# jtag-adapter-1-3.net
KiCad netlist of a schematic drawn in EAGLE
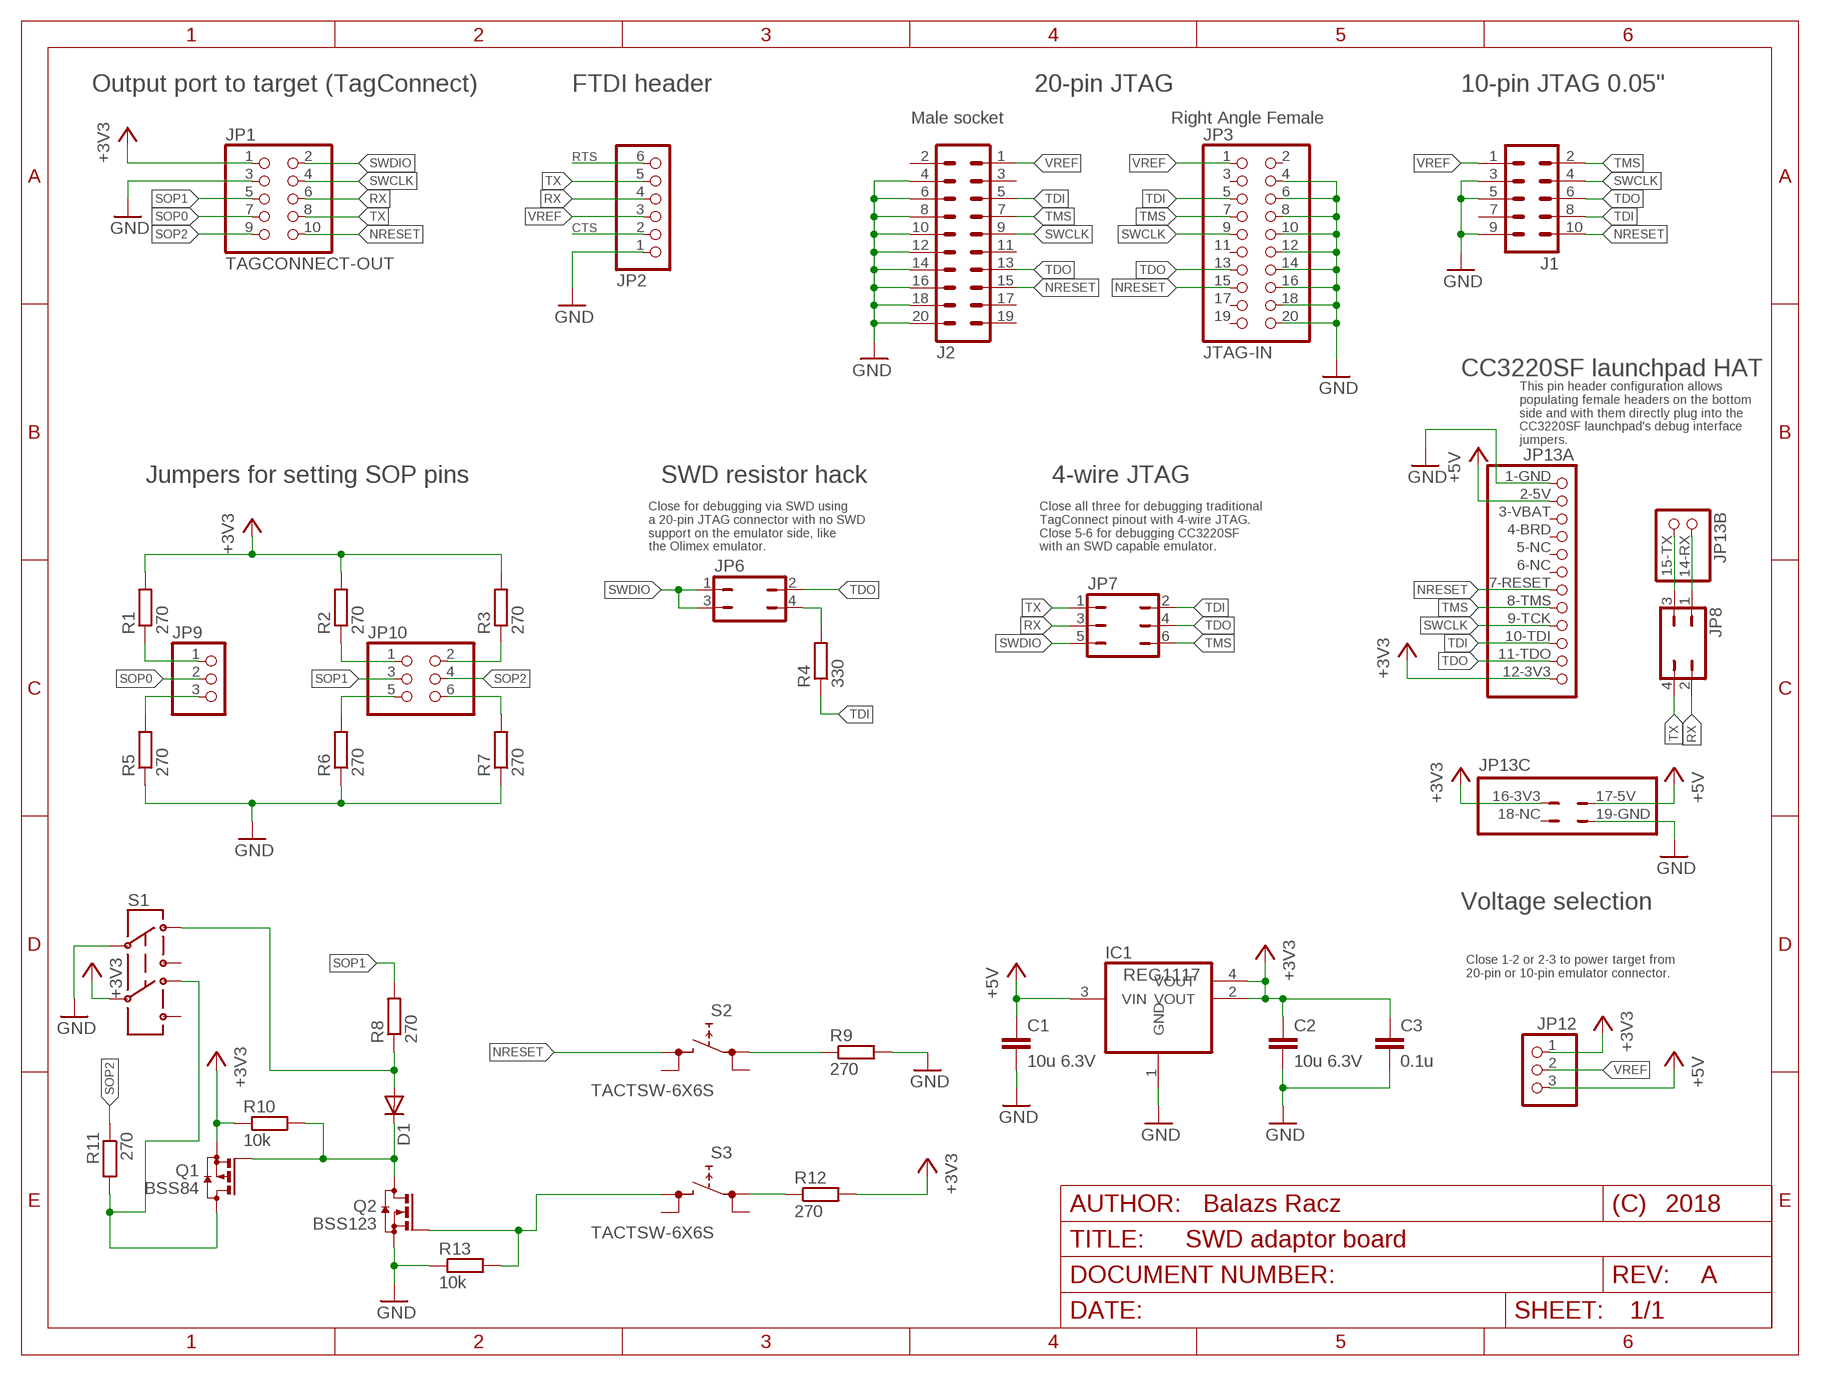
[diagram p0: schematic, sheet 1]

(export (version "E")
  (design (tool "Eeschema 10.0.6"))
  (components
    (comp (ref "C1")
      (value "10u 6.3V")
      (footprint "eagle-import:C0603K")
      (libsource (lib "eagle-import") (part "C-EUC0603K"))
    )
    (comp (ref "C2")
      (value "10u 6.3V")
      (footprint "eagle-import:C0603K")
      (libsource (lib "eagle-import") (part "C-EUC0603K"))
    )
    (comp (ref "C3")
      (value "0.1u")
      (footprint "eagle-import:C0603K")
      (libsource (lib "eagle-import") (part "C-EUC0603K"))
    )
    (comp (ref "D1")
      (value "DIODE-MINIMELF")
      (footprint "eagle-import:MINIMELF")
      (libsource (lib "eagle-import") (part "DIODE-MINIMELF"))
    )
    (comp (ref "IC1")
      (value "REG1117")
      (footprint "eagle-import:SOT223")
      (libsource (lib "eagle-import") (part "REG1117"))
    )
    (comp (ref "J1")
      (value "MA05-2_0.05X0.05")
      (footprint "eagle-import:MA05-2_0.05_X_0.05")
      (libsource (lib "eagle-import") (part "MA05-2_0.05X0.05"))
    )
    (comp (ref "J2")
      (value "MA10-2S")
      (footprint "eagle-import:MA10-2-SHROUDED")
      (libsource (lib "eagle-import") (part "MA10-2S"))
    )
    (comp (ref "JP1")
      (value "TAGCONNECT-OUT")
      (footprint "eagle-import:CON10M")
      (libsource (lib "eagle-import") (part "PINHD-2X5CN"))
    )
    (comp (ref "JP2")
      (value "PINHD-1X6")
      (footprint "eagle-import:1X06")
      (libsource (lib "eagle-import") (part "PINHD-1X6"))
    )
    (comp (ref "JP3")
      (value "JTAG-IN")
      (footprint "eagle-import:2X10_90")
      (libsource (lib "eagle-import") (part "PINHD-2X10/90"))
    )
    (comp (ref "JP6")
      (value "JP2Q")
      (footprint "eagle-import:JP2Q")
      (libsource (lib "eagle-import") (part "JP2Q"))
    )
    (comp (ref "JP7")
      (value "JP3Q")
      (footprint "eagle-import:JP3Q")
      (libsource (lib "eagle-import") (part "JP3Q"))
    )
    (comp (ref "JP8")
      (value "JP2Q")
      (footprint "eagle-import:JP2Q")
      (libsource (lib "eagle-import") (part "JP2Q"))
    )
    (comp (ref "JP9")
      (value "PINHD-1X3")
      (footprint "eagle-import:1X03")
      (libsource (lib "eagle-import") (part "PINHD-1X3"))
    )
    (comp (ref "JP10")
      (value "PINHD-2X3")
      (footprint "eagle-import:2X03")
      (libsource (lib "eagle-import") (part "PINHD-2X3"))
    )
    (comp (ref "JP12")
      (value "PINHD-1X3")
      (footprint "eagle-import:1X03")
      (libsource (lib "eagle-import") (part "PINHD-1X3"))
    )
    (comp (ref "JP13")
      (value "CC3220SF-JTAG-HAT")
      (footprint "eagle-import:JTAG-LAUNCHPAD-3220SF")
      (libsource (lib "eagle-import") (part "CC3220SF-JTAG-HAT"))
    )
    (comp (ref "Q1")
      (value "BSS84")
      (footprint "eagle-import:SOT23")
      (libsource (lib "eagle-import") (part "BSS84"))
    )
    (comp (ref "Q2")
      (value "BSS123")
      (footprint "eagle-import:SOT23")
      (libsource (lib "eagle-import") (part "BSS123"))
    )
    (comp (ref "R1")
      (value "270")
      (footprint "eagle-import:R0805")
      (libsource (lib "eagle-import") (part "R-EU_R0805"))
    )
    (comp (ref "R2")
      (value "270")
      (footprint "eagle-import:R0805")
      (libsource (lib "eagle-import") (part "R-EU_R0805"))
    )
    (comp (ref "R3")
      (value "270")
      (footprint "eagle-import:R0805")
      (libsource (lib "eagle-import") (part "R-EU_R0805"))
    )
    (comp (ref "R4")
      (value "330")
      (footprint "eagle-import:R0805")
      (libsource (lib "eagle-import") (part "R-EU_R0805"))
    )
    (comp (ref "R5")
      (value "270")
      (footprint "eagle-import:R0805")
      (libsource (lib "eagle-import") (part "R-EU_R0805"))
    )
    (comp (ref "R6")
      (value "270")
      (footprint "eagle-import:R0805")
      (libsource (lib "eagle-import") (part "R-EU_R0805"))
    )
    (comp (ref "R7")
      (value "270")
      (footprint "eagle-import:R0805")
      (libsource (lib "eagle-import") (part "R-EU_R0805"))
    )
    (comp (ref "R8")
      (value "270")
      (footprint "eagle-import:R0805")
      (libsource (lib "eagle-import") (part "R-EU_R0805"))
    )
    (comp (ref "R9")
      (value "270")
      (footprint "eagle-import:R0805")
      (libsource (lib "eagle-import") (part "R-EU_R0805"))
    )
    (comp (ref "R10")
      (value "10k")
      (footprint "eagle-import:R0805")
      (libsource (lib "eagle-import") (part "R-EU_R0805"))
    )
    (comp (ref "R11")
      (value "270")
      (footprint "eagle-import:R0805")
      (libsource (lib "eagle-import") (part "R-EU_R0805"))
    )
    (comp (ref "R12")
      (value "270")
      (footprint "eagle-import:R0805")
      (libsource (lib "eagle-import") (part "R-EU_R0805"))
    )
    (comp (ref "R13")
      (value "10k")
      (footprint "eagle-import:R0805")
      (libsource (lib "eagle-import") (part "R-EU_R0805"))
    )
    (comp (ref "S1")
      (value "SWITCH-DPDTJS202011CQN")
      (footprint "eagle-import:DPDT-2.5X3.2MM")
      (libsource (lib "eagle-import") (part "SWITCH-DPDTJS202011CQN"))
    )
    (comp (ref "S2")
      (value "TACTSW-6X6S")
      (footprint "eagle-import:TACTSW-6X6")
      (libsource (lib "eagle-import") (part "TACTSW-6X6S"))
    )
    (comp (ref "S3")
      (value "TACTSW-6X6S")
      (footprint "eagle-import:TACTSW-6X6")
      (libsource (lib "eagle-import") (part "TACTSW-6X6S"))
    )
  )
  (nets
    (net (code "1") (name "+3V3") (class "Default")
      (node (ref "C2") (pin "1") (pinfunction "1_1") (pintype "passive"))
      (node (ref "C3") (pin "1") (pinfunction "1_1") (pintype "passive"))
      (node (ref "IC1") (pin "2") (pinfunction "VOUT_2") (pintype "output"))
      (node (ref "IC1") (pin "4") (pinfunction "VOUT_4") (pintype "output"))
      (node (ref "JP1") (pin "1") (pinfunction "1_1") (pintype "passive"))
      (node (ref "JP12") (pin "1") (pinfunction "1_1") (pintype "passive"))
      (node (ref "JP13") (pin "12-3V3") (pinfunction "12_12-3V3") (pintype "passive"))
      (node (ref "JP13") (pin "16-3V3") (pinfunction "1_16-3V3") (pintype "passive"))
      (node (ref "Q1") (pin "2") (pinfunction "S_2") (pintype "passive"))
      (node (ref "R1") (pin "2") (pinfunction "2_2") (pintype "passive"))
      (node (ref "R10") (pin "1") (pinfunction "1_1") (pintype "passive"))
      (node (ref "R12") (pin "2") (pinfunction "2_2") (pintype "passive"))
      (node (ref "R2") (pin "2") (pinfunction "2_2") (pintype "passive"))
      (node (ref "R3") (pin "2") (pinfunction "2_2") (pintype "passive"))
      (node (ref "S1") (pin "5") (pinfunction "2C_5") (pintype "bidirectional"))
    )
    (net (code "2") (name "+5V") (class "Default")
      (node (ref "C1") (pin "1") (pinfunction "1_1") (pintype "passive"))
      (node (ref "IC1") (pin "3") (pinfunction "VIN_3") (pintype "input"))
      (node (ref "JP12") (pin "3") (pinfunction "3_3") (pintype "passive"))
      (node (ref "JP13") (pin "17-5V") (pinfunction "2_17-5V") (pintype "passive"))
      (node (ref "JP13") (pin "2-5V") (pinfunction "2_2-5V") (pintype "passive"))
    )
    (net (code "3") (name "/CTS") (class "Default")
      (node (ref "JP2") (pin "2") (pinfunction "2_2") (pintype "passive"))
    )
    (net (code "4") (name "/RTS") (class "Default")
      (node (ref "JP2") (pin "6") (pinfunction "6_6") (pintype "passive"))
    )
    (net (code "5") (name "GND") (class "Default")
      (node (ref "C1") (pin "2") (pinfunction "2_2") (pintype "passive"))
      (node (ref "C2") (pin "2") (pinfunction "2_2") (pintype "passive"))
      (node (ref "C3") (pin "2") (pinfunction "2_2") (pintype "passive"))
      (node (ref "IC1") (pin "1") (pinfunction "GND_1") (pintype "power_in"))
      (node (ref "J1") (pin "3") (pinfunction "3_3") (pintype "passive"))
      (node (ref "J1") (pin "5") (pinfunction "5_5") (pintype "passive"))
      (node (ref "J1") (pin "9") (pinfunction "9_9") (pintype "passive"))
      (node (ref "J2") (pin "10") (pinfunction "10_10") (pintype "passive"))
      (node (ref "J2") (pin "12") (pinfunction "12_12") (pintype "passive"))
      (node (ref "J2") (pin "14") (pinfunction "14_14") (pintype "passive"))
      (node (ref "J2") (pin "16") (pinfunction "16_16") (pintype "passive"))
      (node (ref "J2") (pin "18") (pinfunction "18_18") (pintype "passive"))
      (node (ref "J2") (pin "20") (pinfunction "20_20") (pintype "passive"))
      (node (ref "J2") (pin "4") (pinfunction "4_4") (pintype "passive"))
      (node (ref "J2") (pin "6") (pinfunction "6_6") (pintype "passive"))
      (node (ref "J2") (pin "8") (pinfunction "8_8") (pintype "passive"))
      (node (ref "JP1") (pin "3") (pinfunction "3_3") (pintype "passive"))
      (node (ref "JP13") (pin "1-GND") (pinfunction "1_1-GND") (pintype "passive"))
      (node (ref "JP13") (pin "19-GND") (pinfunction "4_19-GND") (pintype "passive"))
      (node (ref "JP2") (pin "1") (pinfunction "1_1") (pintype "passive"))
      (node (ref "JP3") (pin "10") (pinfunction "10_10") (pintype "passive"))
      (node (ref "JP3") (pin "12") (pinfunction "12_12") (pintype "passive"))
      (node (ref "JP3") (pin "14") (pinfunction "14_14") (pintype "passive"))
      (node (ref "JP3") (pin "16") (pinfunction "16_16") (pintype "passive"))
      (node (ref "JP3") (pin "18") (pinfunction "18_18") (pintype "passive"))
      (node (ref "JP3") (pin "20") (pinfunction "20_20") (pintype "passive"))
      (node (ref "JP3") (pin "4") (pinfunction "4_4") (pintype "passive"))
      (node (ref "JP3") (pin "6") (pinfunction "6_6") (pintype "passive"))
      (node (ref "JP3") (pin "8") (pinfunction "8_8") (pintype "passive"))
      (node (ref "Q2") (pin "2") (pinfunction "S_2") (pintype "passive"))
      (node (ref "R13") (pin "1") (pinfunction "1_1") (pintype "passive"))
      (node (ref "R5") (pin "1") (pinfunction "1_1") (pintype "passive"))
      (node (ref "R6") (pin "1") (pinfunction "1_1") (pintype "passive"))
      (node (ref "R7") (pin "1") (pinfunction "1_1") (pintype "passive"))
      (node (ref "R9") (pin "2") (pinfunction "2_2") (pintype "passive"))
      (node (ref "S1") (pin "2") (pinfunction "1C_2") (pintype "bidirectional"))
    )
    (net (code "6") (name "NRESET") (class "Default")
      (node (ref "J1") (pin "10") (pinfunction "10_10") (pintype "passive"))
      (node (ref "J2") (pin "15") (pinfunction "15_15") (pintype "passive"))
      (node (ref "JP1") (pin "10") (pinfunction "10_10") (pintype "passive"))
      (node (ref "JP13") (pin "7-RESET") (pinfunction "7_7-RESET") (pintype "passive"))
      (node (ref "JP3") (pin "15") (pinfunction "15_15") (pintype "passive"))
      (node (ref "S2") (pin "3") (pinfunction "2.1_3") (pintype "passive"))
    )
    (net (code "7") (name "Net-(JP6-Pad4)") (class "Default")
      (node (ref "JP6") (pin "4") (pinfunction "4_4") (pintype "passive"))
      (node (ref "R4") (pin "2") (pinfunction "2_2") (pintype "passive"))
    )
    (net (code "8") (name "Net-(JP9-Pad1)") (class "Default")
      (node (ref "JP9") (pin "1") (pinfunction "1_1") (pintype "passive"))
      (node (ref "R1") (pin "1") (pinfunction "1_1") (pintype "passive"))
    )
    (net (code "9") (name "Net-(JP9-Pad3)") (class "Default")
      (node (ref "JP9") (pin "3") (pinfunction "3_3") (pintype "passive"))
      (node (ref "R5") (pin "2") (pinfunction "2_2") (pintype "passive"))
    )
    (net (code "10") (name "Net-(JP10-Pad1)") (class "Default")
      (node (ref "JP10") (pin "1") (pinfunction "1_1") (pintype "passive"))
      (node (ref "R2") (pin "1") (pinfunction "1_1") (pintype "passive"))
    )
    (net (code "11") (name "Net-(JP10-Pad2)") (class "Default")
      (node (ref "JP10") (pin "2") (pinfunction "2_2") (pintype "passive"))
      (node (ref "R3") (pin "1") (pinfunction "1_1") (pintype "passive"))
    )
    (net (code "12") (name "Net-(JP10-Pad5)") (class "Default")
      (node (ref "JP10") (pin "5") (pinfunction "5_5") (pintype "passive"))
      (node (ref "R6") (pin "2") (pinfunction "2_2") (pintype "passive"))
    )
    (net (code "13") (name "Net-(JP10-Pad6)") (class "Default")
      (node (ref "JP10") (pin "6") (pinfunction "6_6") (pintype "passive"))
      (node (ref "R7") (pin "2") (pinfunction "2_2") (pintype "passive"))
    )
    (net (code "14") (name "Net-(JP13B-1)") (class "Default")
      (node (ref "JP13") (pin "14-RX") (pinfunction "1_14-RX") (pintype "passive"))
      (node (ref "JP8") (pin "1") (pinfunction "1_1") (pintype "passive"))
    )
    (net (code "15") (name "Net-(JP13B-2)") (class "Default")
      (node (ref "JP13") (pin "15-TX") (pinfunction "2_15-TX") (pintype "passive"))
      (node (ref "JP8") (pin "3") (pinfunction "3_3") (pintype "passive"))
    )
    (net (code "16") (name "Net-(Q1-D)") (class "Default")
      (node (ref "Q1") (pin "3") (pinfunction "D_3") (pintype "passive"))
      (node (ref "R11") (pin "2") (pinfunction "2_2") (pintype "passive"))
      (node (ref "S1") (pin "4") (pinfunction "2A_4") (pintype "bidirectional"))
    )
    (net (code "17") (name "Net-(Q1-G)") (class "Default")
      (node (ref "D1") (pin "C") (pinfunction "C_C") (pintype "passive"))
      (node (ref "Q1") (pin "1") (pinfunction "G_1") (pintype "passive"))
      (node (ref "Q2") (pin "3") (pinfunction "D_3") (pintype "passive"))
      (node (ref "R10") (pin "2") (pinfunction "2_2") (pintype "passive"))
    )
    (net (code "18") (name "Net-(Q2-G)") (class "Default")
      (node (ref "Q2") (pin "1") (pinfunction "G_1") (pintype "passive"))
      (node (ref "R13") (pin "2") (pinfunction "2_2") (pintype "passive"))
      (node (ref "S3") (pin "3") (pinfunction "2.1_3") (pintype "passive"))
    )
    (net (code "19") (name "Net-(S1-1A)") (class "Default")
      (node (ref "D1") (pin "A") (pinfunction "A_A") (pintype "passive"))
      (node (ref "R8") (pin "1") (pinfunction "1_1") (pintype "passive"))
      (node (ref "S1") (pin "1") (pinfunction "1A_1") (pintype "bidirectional"))
    )
    (net (code "20") (name "Net-(S2-1.1)") (class "Default")
      (node (ref "R9") (pin "1") (pinfunction "1_1") (pintype "passive"))
      (node (ref "S2") (pin "1") (pinfunction "1.1_1") (pintype "passive"))
    )
    (net (code "21") (name "Net-(S3-1.1)") (class "Default")
      (node (ref "R12") (pin "1") (pinfunction "1_1") (pintype "passive"))
      (node (ref "S3") (pin "1") (pinfunction "1.1_1") (pintype "passive"))
    )
    (net (code "22") (name "RX") (class "Default")
      (node (ref "JP1") (pin "6") (pinfunction "6_6") (pintype "passive"))
      (node (ref "JP2") (pin "4") (pinfunction "4_4") (pintype "passive"))
      (node (ref "JP7") (pin "3") (pinfunction "3_3") (pintype "passive"))
      (node (ref "JP8") (pin "2") (pinfunction "2_2") (pintype "passive"))
    )
    (net (code "23") (name "SOP0") (class "Default")
      (node (ref "JP1") (pin "7") (pinfunction "7_7") (pintype "passive"))
      (node (ref "JP9") (pin "2") (pinfunction "2_2") (pintype "passive"))
    )
    (net (code "24") (name "SOP1") (class "Default")
      (node (ref "JP1") (pin "5") (pinfunction "5_5") (pintype "passive"))
      (node (ref "JP10") (pin "3") (pinfunction "3_3") (pintype "passive"))
      (node (ref "R8") (pin "2") (pinfunction "2_2") (pintype "passive"))
    )
    (net (code "25") (name "SOP2") (class "Default")
      (node (ref "JP1") (pin "9") (pinfunction "9_9") (pintype "passive"))
      (node (ref "JP10") (pin "4") (pinfunction "4_4") (pintype "passive"))
      (node (ref "R11") (pin "1") (pinfunction "1_1") (pintype "passive"))
    )
    (net (code "26") (name "SWCLK") (class "Default")
      (node (ref "J1") (pin "4") (pinfunction "4_4") (pintype "passive"))
      (node (ref "J2") (pin "9") (pinfunction "9_9") (pintype "passive"))
      (node (ref "JP1") (pin "4") (pinfunction "4_4") (pintype "passive"))
      (node (ref "JP13") (pin "9-TCK") (pinfunction "9_9-TCK") (pintype "passive"))
      (node (ref "JP3") (pin "9") (pinfunction "9_9") (pintype "passive"))
    )
    (net (code "27") (name "SWDIO") (class "Default")
      (node (ref "JP1") (pin "2") (pinfunction "2_2") (pintype "passive"))
      (node (ref "JP6") (pin "1") (pinfunction "1_1") (pintype "passive"))
      (node (ref "JP6") (pin "3") (pinfunction "3_3") (pintype "passive"))
      (node (ref "JP7") (pin "5") (pinfunction "5_5") (pintype "passive"))
    )
    (net (code "28") (name "TDI") (class "Default")
      (node (ref "J1") (pin "8") (pinfunction "8_8") (pintype "passive"))
      (node (ref "J2") (pin "5") (pinfunction "5_5") (pintype "passive"))
      (node (ref "JP13") (pin "10-TDI") (pinfunction "10_10-TDI") (pintype "passive"))
      (node (ref "JP3") (pin "5") (pinfunction "5_5") (pintype "passive"))
      (node (ref "JP7") (pin "2") (pinfunction "2_2") (pintype "passive"))
      (node (ref "R4") (pin "1") (pinfunction "1_1") (pintype "passive"))
    )
    (net (code "29") (name "TDO") (class "Default")
      (node (ref "J1") (pin "6") (pinfunction "6_6") (pintype "passive"))
      (node (ref "J2") (pin "13") (pinfunction "13_13") (pintype "passive"))
      (node (ref "JP13") (pin "11-TDO") (pinfunction "11_11-TDO") (pintype "passive"))
      (node (ref "JP3") (pin "13") (pinfunction "13_13") (pintype "passive"))
      (node (ref "JP6") (pin "2") (pinfunction "2_2") (pintype "passive"))
      (node (ref "JP7") (pin "4") (pinfunction "4_4") (pintype "passive"))
    )
    (net (code "30") (name "TMS") (class "Default")
      (node (ref "J1") (pin "2") (pinfunction "2_2") (pintype "passive"))
      (node (ref "J2") (pin "7") (pinfunction "7_7") (pintype "passive"))
      (node (ref "JP13") (pin "8-TMS") (pinfunction "8_8-TMS") (pintype "passive"))
      (node (ref "JP3") (pin "7") (pinfunction "7_7") (pintype "passive"))
      (node (ref "JP7") (pin "6") (pinfunction "6_6") (pintype "passive"))
    )
    (net (code "31") (name "TX") (class "Default")
      (node (ref "JP1") (pin "8") (pinfunction "8_8") (pintype "passive"))
      (node (ref "JP2") (pin "5") (pinfunction "5_5") (pintype "passive"))
      (node (ref "JP7") (pin "1") (pinfunction "1_1") (pintype "passive"))
      (node (ref "JP8") (pin "4") (pinfunction "4_4") (pintype "passive"))
    )
    (net (code "32") (name "VREF") (class "Default")
      (node (ref "J1") (pin "1") (pinfunction "1_1") (pintype "passive"))
      (node (ref "J2") (pin "1") (pinfunction "1_1") (pintype "passive"))
      (node (ref "JP12") (pin "2") (pinfunction "2_2") (pintype "passive"))
      (node (ref "JP2") (pin "3") (pinfunction "3_3") (pintype "passive"))
      (node (ref "JP3") (pin "1") (pinfunction "1_1") (pintype "passive"))
    )
    (net (code "33") (name "unconnected-(J1-Pad7)") (class "Default")
      (node (ref "J1") (pin "7") (pinfunction "7_7") (pintype "passive"))
    )
    (net (code "34") (name "unconnected-(J2-Pad2)") (class "Default")
      (node (ref "J2") (pin "2") (pinfunction "2_2") (pintype "passive"))
    )
    (net (code "35") (name "unconnected-(J2-Pad3)") (class "Default")
      (node (ref "J2") (pin "3") (pinfunction "3_3") (pintype "passive"))
    )
    (net (code "36") (name "unconnected-(J2-Pad11)") (class "Default")
      (node (ref "J2") (pin "11") (pinfunction "11_11") (pintype "passive"))
    )
    (net (code "37") (name "unconnected-(J2-Pad17)") (class "Default")
      (node (ref "J2") (pin "17") (pinfunction "17_17") (pintype "passive"))
    )
    (net (code "38") (name "unconnected-(J2-Pad19)") (class "Default")
      (node (ref "J2") (pin "19") (pinfunction "19_19") (pintype "passive"))
    )
    (net (code "39") (name "unconnected-(JP3-Pad2)") (class "Default")
      (node (ref "JP3") (pin "2") (pinfunction "2_2") (pintype "passive"))
    )
    (net (code "40") (name "unconnected-(JP3-Pad3)") (class "Default")
      (node (ref "JP3") (pin "3") (pinfunction "3_3") (pintype "passive"))
    )
    (net (code "41") (name "unconnected-(JP3-Pad11)") (class "Default")
      (node (ref "JP3") (pin "11") (pinfunction "11_11") (pintype "passive"))
    )
    (net (code "42") (name "unconnected-(JP3-Pad17)") (class "Default")
      (node (ref "JP3") (pin "17") (pinfunction "17_17") (pintype "passive"))
    )
    (net (code "43") (name "unconnected-(JP3-Pad19)") (class "Default")
      (node (ref "JP3") (pin "19") (pinfunction "19_19") (pintype "passive"))
    )
    (net (code "44") (name "unconnected-(JP13A-3-Pad3-VBAT)") (class "Default")
      (node (ref "JP13") (pin "3-VBAT") (pinfunction "3_3-VBAT") (pintype "passive"))
    )
    (net (code "45") (name "unconnected-(JP13A-4-Pad4-BRD)") (class "Default")
      (node (ref "JP13") (pin "4-BRD") (pinfunction "4_4-BRD") (pintype "passive"))
    )
    (net (code "46") (name "unconnected-(JP13A-5-Pad5-NC)") (class "Default")
      (node (ref "JP13") (pin "5-NC") (pinfunction "5_5-NC") (pintype "passive"))
    )
    (net (code "47") (name "unconnected-(JP13A-6-Pad6-NC)") (class "Default")
      (node (ref "JP13") (pin "6-NC") (pinfunction "6_6-NC") (pintype "passive"))
    )
    (net (code "48") (name "unconnected-(JP13C-3-Pad18-NC)") (class "Default")
      (node (ref "JP13") (pin "18-NC") (pinfunction "3_18-NC") (pintype "passive"))
    )
    (net (code "49") (name "unconnected-(S1-1B-Pad3)") (class "Default")
      (node (ref "S1") (pin "3") (pinfunction "1B_3") (pintype "bidirectional"))
    )
    (net (code "50") (name "unconnected-(S1-2B-Pad6)") (class "Default")
      (node (ref "S1") (pin "6") (pinfunction "2B_6") (pintype "bidirectional"))
    )
    (net (code "51") (name "unconnected-(S2-1.2-Pad2)") (class "Default")
      (node (ref "S2") (pin "2") (pinfunction "1.2_2") (pintype "passive"))
    )
    (net (code "52") (name "unconnected-(S2-2.2-Pad4)") (class "Default")
      (node (ref "S2") (pin "4") (pinfunction "2.2_4") (pintype "passive"))
    )
    (net (code "53") (name "unconnected-(S3-1.2-Pad2)") (class "Default")
      (node (ref "S3") (pin "2") (pinfunction "1.2_2") (pintype "passive"))
    )
    (net (code "54") (name "unconnected-(S3-2.2-Pad4)") (class "Default")
      (node (ref "S3") (pin "4") (pinfunction "2.2_4") (pintype "passive"))
    )
  )
)
